# Adafruit_INA3221_Breakout.net
KiCad netlist of a schematic drawn in EAGLE
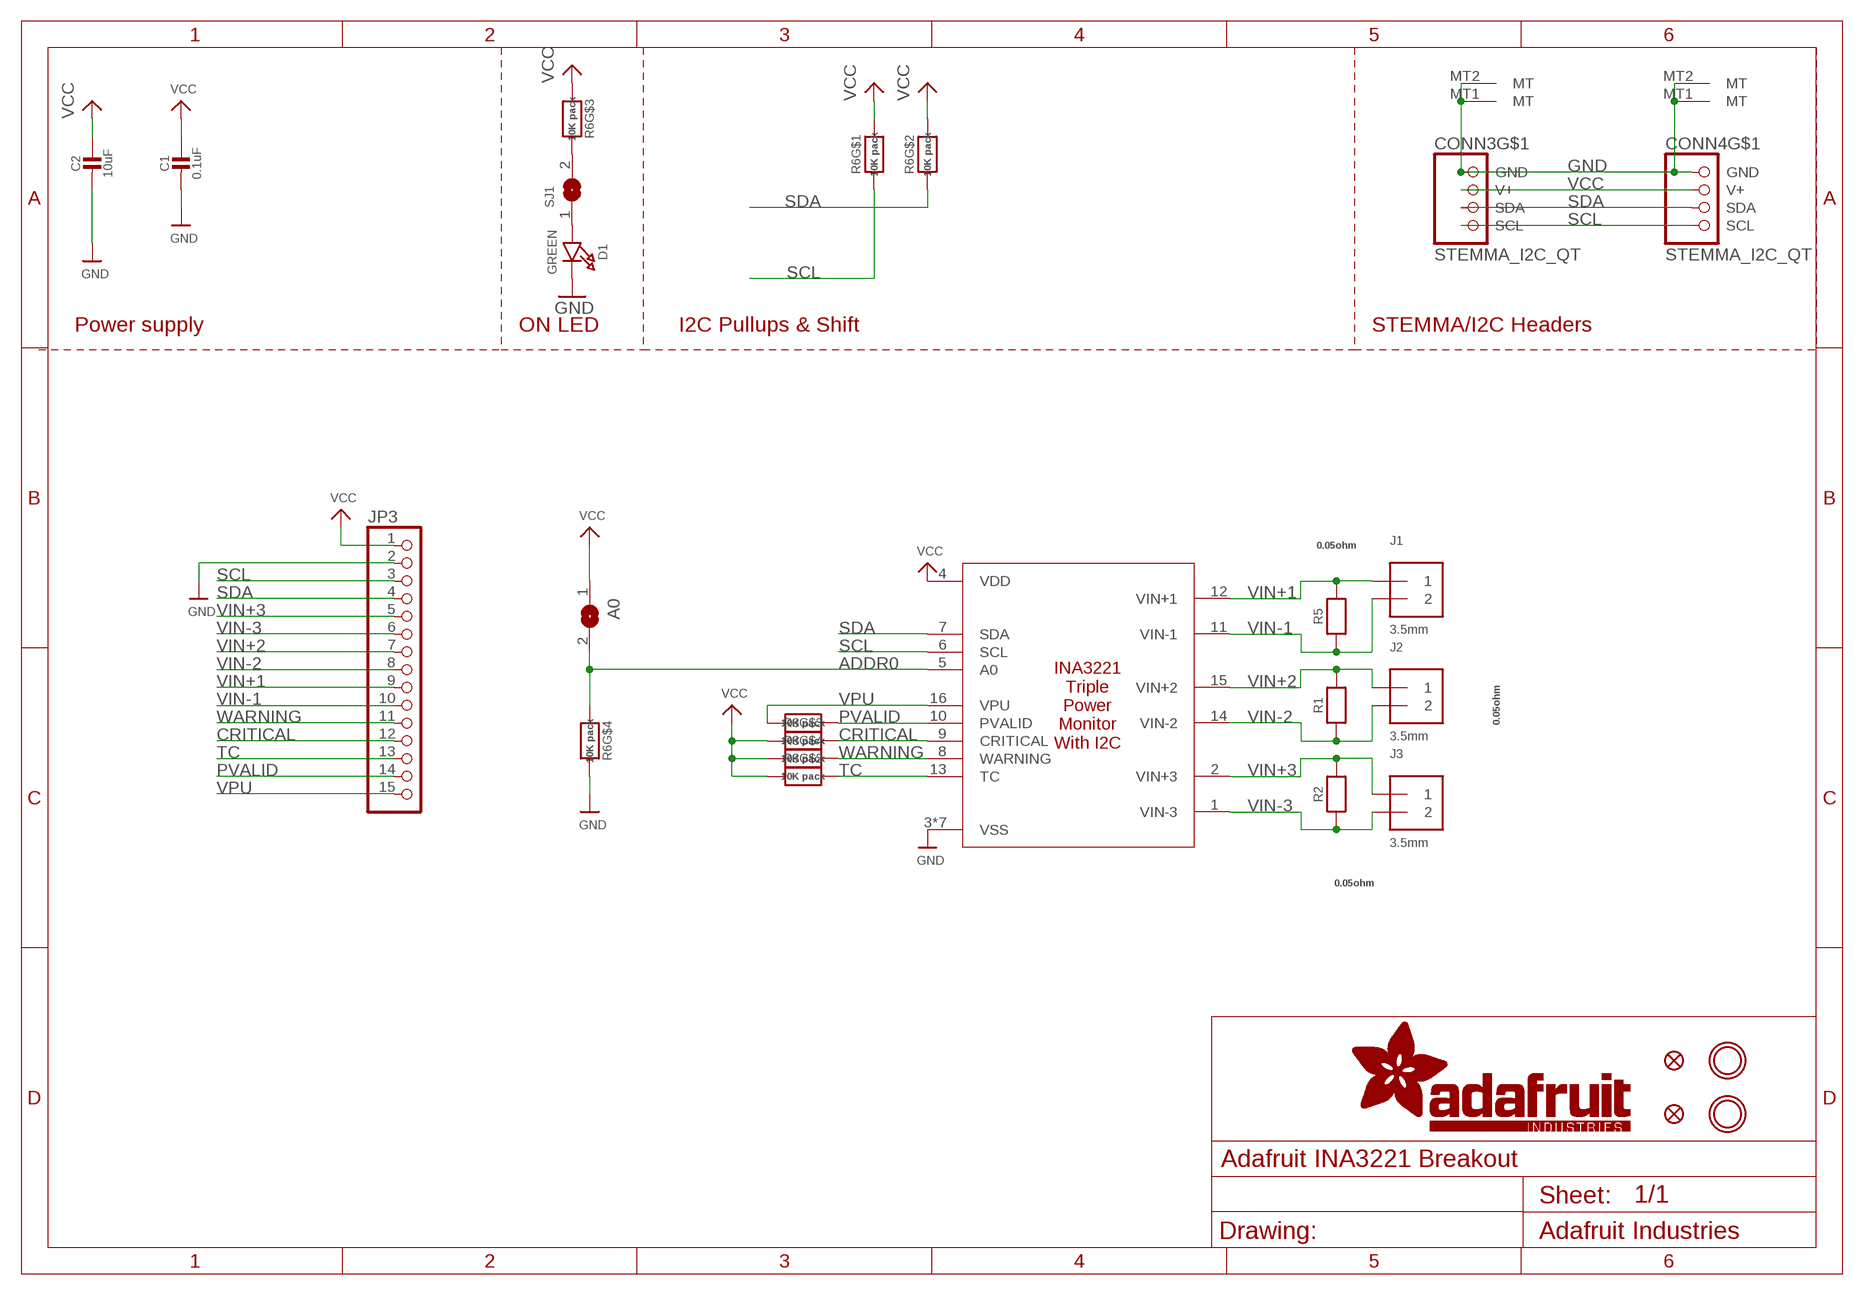
[diagram p0: schematic, sheet 1]

(export (version "E")
  (design (tool "Eeschema 10.0.6"))
  (components
    (comp (ref "A0")
      (value "SOLDERJUMPERREFLOW_NOPASTE")
      (footprint "eagle-import:SOLDERJUMPER_REFLOW_NOPASTE")
      (libsource (lib "eagle-import") (part "SOLDERJUMPERREFLOW_NOPASTE"))
    )
    (comp (ref "C1")
      (value "0.1uF")
      (footprint "eagle-import:0603-NO")
      (libsource (lib "eagle-import") (part "CAP_CERAMIC0603_NO"))
    )
    (comp (ref "C2")
      (value "10uF")
      (footprint "eagle-import:0805-NO")
      (libsource (lib "eagle-import") (part "CAP_CERAMIC0805-NOOUTLINE"))
    )
    (comp (ref "CONN3")
      (value "STEMMA_I2C_QT")
      (footprint "eagle-import:JST_SH4")
      (libsource (lib "eagle-import") (part "STEMMA_I2C_QT"))
    )
    (comp (ref "CONN4")
      (value "STEMMA_I2C_QT")
      (footprint "eagle-import:JST_SH4")
      (libsource (lib "eagle-import") (part "STEMMA_I2C_QT"))
    )
    (comp (ref "D1")
      (value "GREEN")
      (footprint "eagle-import:CHIPLED_0603_NOOUTLINE")
      (libsource (lib "eagle-import") (part "LED0603_NOOUTLINE"))
    )
    (comp (ref "FID3")
      (value "FIDUCIAL_1MM")
      (footprint "eagle-import:FIDUCIAL_1MM")
      (libsource (lib "eagle-import") (part "FIDUCIAL_1MM"))
    )
    (comp (ref "FID4")
      (value "FIDUCIAL_1MM")
      (footprint "eagle-import:FIDUCIAL_1MM")
      (libsource (lib "eagle-import") (part "FIDUCIAL_1MM"))
    )
    (comp (ref "IC1")
      (value "INA3221")
      (footprint "eagle-import:PVQFN-16")
      (libsource (lib "eagle-import") (part "INA3221"))
    )
    (comp (ref "J1")
      (value "3.5mm")
      (footprint "eagle-import:TERMBLOCK_1X2-3.5MM")
      (libsource (lib "eagle-import") (part "TERMBLOCK_1X2_3.5MM"))
    )
    (comp (ref "J2")
      (value "3.5mm")
      (footprint "eagle-import:TERMBLOCK_1X2-3.5MM")
      (libsource (lib "eagle-import") (part "TERMBLOCK_1X2_3.5MM"))
    )
    (comp (ref "J3")
      (value "3.5mm")
      (footprint "eagle-import:TERMBLOCK_1X2-3.5MM")
      (libsource (lib "eagle-import") (part "TERMBLOCK_1X2_3.5MM"))
    )
    (comp (ref "JP3")
      (value "HEADER-1X15")
      (footprint "eagle-import:1X15_ROUND_70")
      (libsource (lib "eagle-import") (part "HEADER-1X15"))
    )
    (comp (ref "R1")
      (value "0.05ohm")
      (footprint "eagle-import:_1206")
      (libsource (lib "eagle-import") (part "RESISTOR_1206"))
    )
    (comp (ref "R2")
      (value "0.05ohm")
      (footprint "eagle-import:_1206")
      (libsource (lib "eagle-import") (part "RESISTOR_1206"))
    )
    (comp (ref "R3")
      (value "10K pack")
      (footprint "eagle-import:RESPACK_4X0603")
      (libsource (lib "eagle-import") (part "RESISTOR_4PACK"))
    )
    (comp (ref "R5")
      (value "0.05ohm")
      (footprint "eagle-import:_1206")
      (libsource (lib "eagle-import") (part "RESISTOR_1206"))
    )
    (comp (ref "R6")
      (value "10K pack")
      (footprint "eagle-import:RESPACK_4X0603")
      (libsource (lib "eagle-import") (part "RESISTOR_4PACK"))
    )
    (comp (ref "SJ1")
      (value "SOLDERJUMPERCLOSED")
      (footprint "eagle-import:SOLDERJUMPER_CLOSEDWIRE")
      (libsource (lib "eagle-import") (part "SOLDERJUMPERCLOSED"))
    )
    (comp (ref "U$20")
      (value "MOUNTINGHOLE2.5")
      (footprint "eagle-import:MOUNTINGHOLE_2.5_PLATED")
      (libsource (lib "eagle-import") (part "MOUNTINGHOLE2.5"))
    )
    (comp (ref "U$21")
      (value "MOUNTINGHOLE2.5")
      (footprint "eagle-import:MOUNTINGHOLE_2.5_PLATED")
      (libsource (lib "eagle-import") (part "MOUNTINGHOLE2.5"))
    )
  )
  (nets
    (net (code "1") (name "/ADDR0") (class "Default")
      (node (ref "A0") (pin "2") (pinfunction "2_2") (pintype "passive"))
      (node (ref "IC1") (pin "5") (pinfunction "A0_5") (pintype "input"))
      (node (ref "R6") (pin "4") (pinfunction "1_4") (pintype "passive"))
    )
    (net (code "2") (name "/CRITICAL") (class "Default")
      (node (ref "IC1") (pin "9") (pinfunction "CRITICAL_9") (pintype "output"))
      (node (ref "JP3") (pin "12") (pinfunction "12_12") (pintype "passive"))
      (node (ref "R3") (pin "6") (pinfunction "2_6") (pintype "passive"))
    )
    (net (code "3") (name "/PVALID") (class "Default")
      (node (ref "IC1") (pin "10") (pinfunction "PVALID_10") (pintype "output"))
      (node (ref "JP3") (pin "14") (pinfunction "14_14") (pintype "passive"))
      (node (ref "R3") (pin "8") (pinfunction "2_8") (pintype "passive"))
    )
    (net (code "4") (name "/SCL") (class "Default")
      (node (ref "CONN3") (pin "4") (pinfunction "SCL_4") (pintype "passive"))
      (node (ref "CONN4") (pin "4") (pinfunction "SCL_4") (pintype "passive"))
      (node (ref "IC1") (pin "6") (pinfunction "SCL_6") (pintype "bidirectional"))
      (node (ref "JP3") (pin "3") (pinfunction "3_3") (pintype "passive"))
      (node (ref "R6") (pin "1") (pinfunction "1_1") (pintype "passive"))
    )
    (net (code "5") (name "/SDA") (class "Default")
      (node (ref "CONN3") (pin "3") (pinfunction "SDA_3") (pintype "passive"))
      (node (ref "CONN4") (pin "3") (pinfunction "SDA_3") (pintype "passive"))
      (node (ref "IC1") (pin "7") (pinfunction "SDA_7") (pintype "bidirectional"))
      (node (ref "JP3") (pin "4") (pinfunction "4_4") (pintype "passive"))
      (node (ref "R6") (pin "2") (pinfunction "1_2") (pintype "passive"))
    )
    (net (code "6") (name "/TC") (class "Default")
      (node (ref "IC1") (pin "13") (pinfunction "TC_13") (pintype "output"))
      (node (ref "JP3") (pin "13") (pinfunction "13_13") (pintype "passive"))
      (node (ref "R3") (pin "7") (pinfunction "2_7") (pintype "passive"))
    )
    (net (code "7") (name "/VIN+1") (class "Default")
      (node (ref "IC1") (pin "12") (pinfunction "VIN+1_12") (pintype "input"))
      (node (ref "J1") (pin "1") (pinfunction "1_1") (pintype "passive"))
      (node (ref "JP3") (pin "9") (pinfunction "9_9") (pintype "passive"))
      (node (ref "R5") (pin "2") (pinfunction "2_2") (pintype "passive"))
    )
    (net (code "8") (name "/VIN+2") (class "Default")
      (node (ref "IC1") (pin "15") (pinfunction "VIN+2_15") (pintype "input"))
      (node (ref "J2") (pin "1") (pinfunction "1_1") (pintype "passive"))
      (node (ref "JP3") (pin "7") (pinfunction "7_7") (pintype "passive"))
      (node (ref "R1") (pin "2") (pinfunction "2_2") (pintype "passive"))
    )
    (net (code "9") (name "/VIN+3") (class "Default")
      (node (ref "IC1") (pin "2") (pinfunction "VIN+3_2") (pintype "input"))
      (node (ref "J3") (pin "1") (pinfunction "1_1") (pintype "passive"))
      (node (ref "JP3") (pin "5") (pinfunction "5_5") (pintype "passive"))
      (node (ref "R2") (pin "2") (pinfunction "2_2") (pintype "passive"))
    )
    (net (code "10") (name "/VIN-1") (class "Default")
      (node (ref "IC1") (pin "11") (pinfunction "VIN-1_11") (pintype "input"))
      (node (ref "J1") (pin "2") (pinfunction "2_2") (pintype "passive"))
      (node (ref "JP3") (pin "10") (pinfunction "10_10") (pintype "passive"))
      (node (ref "R5") (pin "1") (pinfunction "1_1") (pintype "passive"))
    )
    (net (code "11") (name "/VIN-2") (class "Default")
      (node (ref "IC1") (pin "14") (pinfunction "VIN-2_14") (pintype "input"))
      (node (ref "J2") (pin "2") (pinfunction "2_2") (pintype "passive"))
      (node (ref "JP3") (pin "8") (pinfunction "8_8") (pintype "passive"))
      (node (ref "R1") (pin "1") (pinfunction "1_1") (pintype "passive"))
    )
    (net (code "12") (name "/VIN-3") (class "Default")
      (node (ref "IC1") (pin "1") (pinfunction "VIN-3_1") (pintype "input"))
      (node (ref "J3") (pin "2") (pinfunction "2_2") (pintype "passive"))
      (node (ref "JP3") (pin "6") (pinfunction "6_6") (pintype "passive"))
      (node (ref "R2") (pin "1") (pinfunction "1_1") (pintype "passive"))
    )
    (net (code "13") (name "/VPU") (class "Default")
      (node (ref "IC1") (pin "16") (pinfunction "VPU_16") (pintype "input"))
      (node (ref "JP3") (pin "15") (pinfunction "15_15") (pintype "passive"))
      (node (ref "R3") (pin "1") (pinfunction "1_1") (pintype "passive"))
    )
    (net (code "14") (name "/WARNING") (class "Default")
      (node (ref "IC1") (pin "8") (pinfunction "WARNING_8") (pintype "output"))
      (node (ref "JP3") (pin "11") (pinfunction "11_11") (pintype "passive"))
      (node (ref "R3") (pin "5") (pinfunction "2_5") (pintype "passive"))
    )
    (net (code "15") (name "GND") (class "Default")
      (node (ref "C1") (pin "2") (pinfunction "2_2") (pintype "passive"))
      (node (ref "C2") (pin "2") (pinfunction "2_2") (pintype "passive"))
      (node (ref "CONN3") (pin "1") (pinfunction "GND_1") (pintype "passive"))
      (node (ref "CONN3") (pin "MT1") (pinfunction "MT_MT1") (pintype "bidirectional"))
      (node (ref "CONN3") (pin "MT2") (pinfunction "MT_MT2") (pintype "bidirectional"))
      (node (ref "CONN4") (pin "1") (pinfunction "GND_1") (pintype "passive"))
      (node (ref "CONN4") (pin "MT1") (pinfunction "MT_MT1") (pintype "bidirectional"))
      (node (ref "CONN4") (pin "MT2") (pinfunction "MT_MT2") (pintype "bidirectional"))
      (node (ref "D1") (pin "C") (pinfunction "C_C") (pintype "passive"))
      (node (ref "IC1") (pin "3") (pinfunction "VSS_3") (pintype "power_in"))
      (node (ref "IC1") (pin "P$18") (pinfunction "VSS_P$18") (pintype "power_in"))
      (node (ref "IC1") (pin "P$19") (pinfunction "VSS_P$19") (pintype "power_in"))
      (node (ref "IC1") (pin "P$20") (pinfunction "VSS_P$20") (pintype "power_in"))
      (node (ref "IC1") (pin "P$21") (pinfunction "VSS_P$21") (pintype "power_in"))
      (node (ref "IC1") (pin "P$22") (pinfunction "VSS_P$22") (pintype "power_in"))
      (node (ref "IC1") (pin "THERMAL") (pinfunction "VSS_THERMAL") (pintype "power_in"))
      (node (ref "JP3") (pin "2") (pinfunction "2_2") (pintype "passive"))
      (node (ref "R6") (pin "5") (pinfunction "2_5") (pintype "passive"))
    )
    (net (code "16") (name "Net-(D1-PadA)") (class "Default")
      (node (ref "D1") (pin "A") (pinfunction "A_A") (pintype "passive"))
      (node (ref "SJ1") (pin "1") (pinfunction "1_1") (pintype "passive"))
    )
    (net (code "17") (name "Net-(R6C-2)") (class "Default")
      (node (ref "R6") (pin "6") (pinfunction "2_6") (pintype "passive"))
      (node (ref "SJ1") (pin "2") (pinfunction "2_2") (pintype "passive"))
    )
    (net (code "18") (name "VCC") (class "Default")
      (node (ref "A0") (pin "1") (pinfunction "1_1") (pintype "passive"))
      (node (ref "C1") (pin "1") (pinfunction "1_1") (pintype "passive"))
      (node (ref "C2") (pin "1") (pinfunction "1_1") (pintype "passive"))
      (node (ref "CONN3") (pin "2") (pinfunction "V+_2") (pintype "passive"))
      (node (ref "CONN4") (pin "2") (pinfunction "V+_2") (pintype "passive"))
      (node (ref "IC1") (pin "4") (pinfunction "VDD_4") (pintype "power_in"))
      (node (ref "JP3") (pin "1") (pinfunction "1_1") (pintype "passive"))
      (node (ref "R3") (pin "2") (pinfunction "1_2") (pintype "passive"))
      (node (ref "R3") (pin "3") (pinfunction "1_3") (pintype "passive"))
      (node (ref "R3") (pin "4") (pinfunction "1_4") (pintype "passive"))
      (node (ref "R6") (pin "3") (pinfunction "1_3") (pintype "passive"))
      (node (ref "R6") (pin "7") (pinfunction "2_7") (pintype "passive"))
      (node (ref "R6") (pin "8") (pinfunction "2_8") (pintype "passive"))
    )
  )
)
